# LM704A0_5V0_PINOUT.net
KiCad netlist of a schematic drawn in Altium Designer
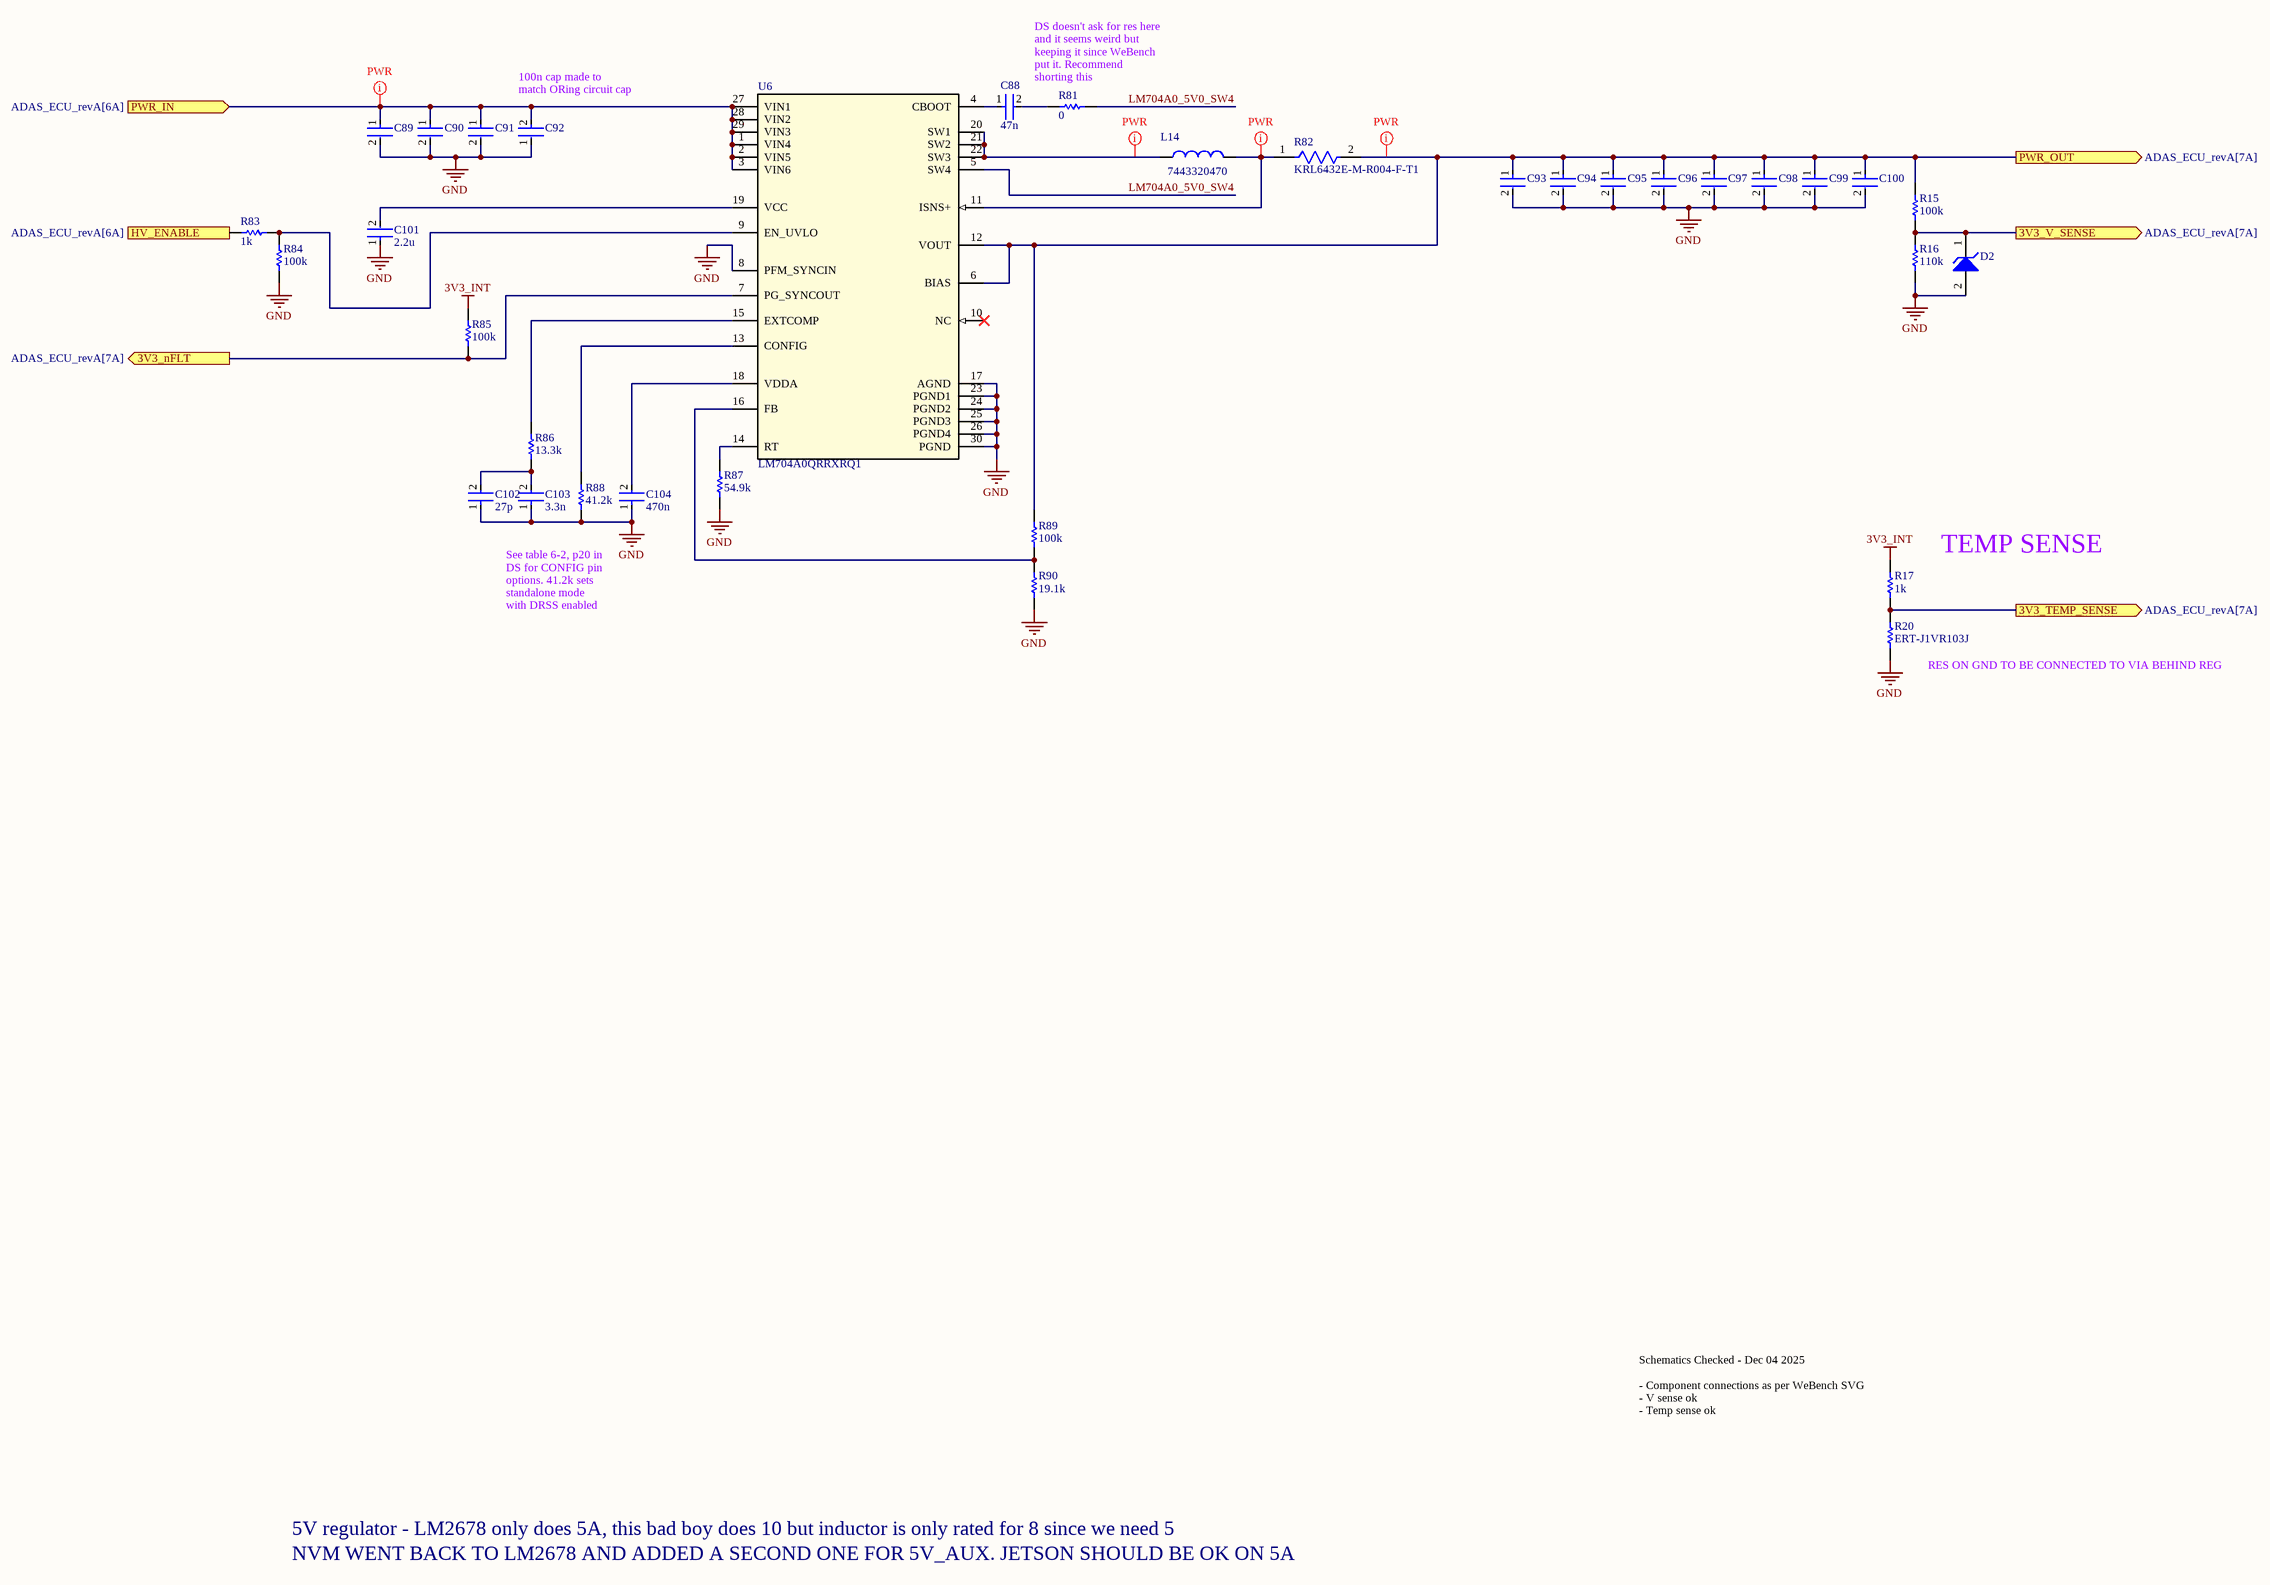
[diagram p0: LM704A0_5V0_PINOUT.SchDoc]

(export (version "E")
  (design (tool "Eeschema 10.0.6"))
  (components
    (comp (ref "C88")
      (value "47n")
      (footprint "FP-0402-L_1_0_0_05-W_0_5-IPC_A")
      (description "LARGE PADS, 0402 CAP, CHANGE COMMENT TO MATCH REAL P/N")
      (libsource (lib "Space Concordia") (part "b4654b650e69147ec39a6b967a45e02"))
    )
    (comp (ref "C89")
      (value "C3225X7R1H106M250AC")
      (footprint "FP-C3225-250-0_4-MFG")
      (description "Multilayer Ceramic Capacitors 10uF ±20% 50V X7R SMD 1210")
      (fields (field (name "TOLERANCE") "20%"))
      (libsource (lib "Altium Content Vault") (part "02cd4be3c70576c341d710602a673aa"))
    )
    (comp (ref "C90")
      (value "C3225X7R1H106M250AC")
      (footprint "FP-C3225-250-0_4-MFG")
      (description "Multilayer Ceramic Capacitors 10uF ±20% 50V X7R SMD 1210")
      (fields (field (name "TOLERANCE") "20%"))
      (libsource (lib "Altium Content Vault") (part "02cd4be3c70576c341d710602a673aa"))
    )
    (comp (ref "C91")
      (value "C3225X7R1H106M250AC")
      (footprint "FP-C3225-250-0_4-MFG")
      (description "Multilayer Ceramic Capacitors 10uF ±20% 50V X7R SMD 1210")
      (fields (field (name "TOLERANCE") "20%"))
      (libsource (lib "Altium Content Vault") (part "02cd4be3c70576c341d710602a673aa"))
    )
    (comp (ref "C92")
      (value "AC1210KKX7R0BB104")
      (footprint "FP-AC1210-0_85-MFG")
      (description "CAP CER 0.1UF 100V X7R 1210")
      (fields (field (name "MANUFACTURER") "Yageo") (field (name "TOLERANCE") "0.1"))
      (libsource (lib "Altium Content Vault") (part "236180d848d6139a670b325ea6854c9"))
    )
    (comp (ref "C93")
      (value "GRM32ER61C476KE15L")
      (footprint "FP-GRM32E-0_3-0_2-IPC_C")
      (description "CAP CER 47UF 16V X5R 1210")
      (fields (field (name "VOLTAGE") "16V") (field (name "TOLERANCE") "10%"))
      (libsource (lib "Altium Content Vault") (part "b4654b650e69147ec39a6b967a45e02"))
    )
    (comp (ref "C94")
      (value "GRM32ER61C476KE15L")
      (footprint "FP-GRM32E-0_3-0_2-IPC_C")
      (description "CAP CER 47UF 16V X5R 1210")
      (fields (field (name "VOLTAGE") "16V") (field (name "TOLERANCE") "10%"))
      (libsource (lib "Altium Content Vault") (part "b4654b650e69147ec39a6b967a45e02"))
    )
    (comp (ref "C95")
      (value "GRM32ER61C476KE15L")
      (footprint "FP-GRM32E-0_3-0_2-IPC_C")
      (description "CAP CER 47UF 16V X5R 1210")
      (fields (field (name "VOLTAGE") "16V") (field (name "TOLERANCE") "10%"))
      (libsource (lib "Altium Content Vault") (part "b4654b650e69147ec39a6b967a45e02"))
    )
    (comp (ref "C96")
      (value "GRM32ER61C476KE15L")
      (footprint "FP-GRM32E-0_3-0_2-IPC_C")
      (description "CAP CER 47UF 16V X5R 1210")
      (fields (field (name "VOLTAGE") "16V") (field (name "TOLERANCE") "10%"))
      (libsource (lib "Altium Content Vault") (part "b4654b650e69147ec39a6b967a45e02"))
    )
    (comp (ref "C97")
      (value "GRM32ER61C476KE15L")
      (footprint "FP-GRM32E-0_3-0_2-IPC_C")
      (description "CAP CER 47UF 16V X5R 1210")
      (fields (field (name "VOLTAGE") "16V") (field (name "TOLERANCE") "10%"))
      (libsource (lib "Altium Content Vault") (part "b4654b650e69147ec39a6b967a45e02"))
    )
    (comp (ref "C98")
      (value "GRM32ER61C476KE15L")
      (footprint "FP-GRM32E-0_3-0_2-IPC_C")
      (description "CAP CER 47UF 16V X5R 1210")
      (fields (field (name "VOLTAGE") "16V") (field (name "TOLERANCE") "10%"))
      (libsource (lib "Altium Content Vault") (part "b4654b650e69147ec39a6b967a45e02"))
    )
    (comp (ref "C99")
      (value "GRM32ER61C476KE15L")
      (footprint "FP-GRM32E-0_3-0_2-IPC_C")
      (description "CAP CER 47UF 16V X5R 1210")
      (fields (field (name "VOLTAGE") "16V") (field (name "TOLERANCE") "10%"))
      (libsource (lib "Altium Content Vault") (part "b4654b650e69147ec39a6b967a45e02"))
    )
    (comp (ref "C100")
      (value "GRM32ER61C476KE15L")
      (footprint "FP-GRM32E-0_3-0_2-IPC_C")
      (description "CAP CER 47UF 16V X5R 1210")
      (fields (field (name "VOLTAGE") "16V") (field (name "TOLERANCE") "10%"))
      (libsource (lib "Altium Content Vault") (part "b4654b650e69147ec39a6b967a45e02"))
    )
    (comp (ref "C101")
      (value "2.2u")
      (footprint "FP-0402-L_1_0_0_05-W_0_5-IPC_A")
      (description "LARGE PADS, 0402 CAP, CHANGE COMMENT TO MATCH REAL P/N")
      (libsource (lib "Space Concordia") (part "b4654b650e69147ec39a6b967a45e02"))
    )
    (comp (ref "C102")
      (value "27p")
      (footprint "FP-0402-L_1_0_0_05-W_0_5-IPC_A")
      (description "LARGE PADS, 0402 CAP, CHANGE COMMENT TO MATCH REAL P/N")
      (libsource (lib "Space Concordia") (part "b4654b650e69147ec39a6b967a45e02"))
    )
    (comp (ref "C103")
      (value "3.3n")
      (footprint "FP-0402-L_1_0_0_05-W_0_5-IPC_A")
      (description "LARGE PADS, 0402 CAP, CHANGE COMMENT TO MATCH REAL P/N")
      (libsource (lib "Space Concordia") (part "b4654b650e69147ec39a6b967a45e02"))
    )
    (comp (ref "C104")
      (value "470n")
      (footprint "FP-0402-L_1_0_0_05-W_0_5-IPC_A")
      (description "LARGE PADS, 0402 CAP, CHANGE COMMENT TO MATCH REAL P/N")
      (libsource (lib "Space Concordia") (part "b4654b650e69147ec39a6b967a45e02"))
    )
    (comp (ref "D2")
      (value "MM5Z3V3T1G")
      (footprint "ONSC-SOD-523-2-502-01_V")
      (description "Zener Voltage Regulator, 500 mW, 2-Pin SOD-523, Pb-Free, Tape and Reel")
      (fields (field (name "MANUFACTURER") "On Semiconductor"))
      (libsource (lib "Altium Content Vault") (part "ONSC-K1A2-2"))
    )
    (comp (ref "L14")
      (value "7443320470")
      (footprint "WE-HCC_1210")
      (description "We-hcc Series, Shielded Wire-wound SMD Inductor With Ferrite Core, 4.7 Uh")
      (libsource (lib "Altium Content Vault") (part "Inductor - 1"))
    )
    (comp (ref "R15")
      (value "100k")
      (footprint "R0603B")
      (description "Resistor")
      (libsource (lib "Space Concordia") (part "Resistor"))
    )
    (comp (ref "R16")
      (value "110k")
      (footprint "R0603B")
      (description "Resistor")
      (libsource (lib "Space Concordia") (part "Resistor"))
    )
    (comp (ref "R17")
      (value "1k")
      (footprint "R0603B")
      (description "Resistor")
      (libsource (lib "Space Concordia") (part "Resistor"))
    )
    (comp (ref "R20")
      (value "ERT-J1VR103J")
      (footprint "RESC1608X90X30ML15T20")
      (fields (field (name "MANUFACTURER") "Panasonic"))
      (libsource (lib "Altium Content Vault") (part "RES"))
    )
    (comp (ref "R81")
      (value "0")
      (footprint "R0603B")
      (description "Resistor")
      (libsource (lib "Space Concordia") (part "Resistor"))
    )
    (comp (ref "R82")
      (value "KRL6432E-M-R004-F-T1")
      (footprint "FP-KRL6432E-MFG")
      (description "KRL6432E-M-R004-F-T1 Metal Foil Low Resistance Chip Resistor (long-side terminal), 2512, RoHS")
      (fields (field (name "TOLERANCE") "1%"))
      (libsource (lib "Altium Content Vault") (part "1029c3af85768c4190bb7ad29bc67b5"))
    )
    (comp (ref "R83")
      (value "1k")
      (footprint "R0603B")
      (description "Resistor")
      (libsource (lib "Space Concordia") (part "Resistor"))
    )
    (comp (ref "R84")
      (value "100k")
      (footprint "R0603B")
      (description "Resistor")
      (libsource (lib "Space Concordia") (part "Resistor"))
    )
    (comp (ref "R85")
      (value "100k")
      (footprint "R0603B")
      (description "Resistor")
      (libsource (lib "Space Concordia") (part "Resistor"))
    )
    (comp (ref "R86")
      (value "13.3k")
      (footprint "R0603B")
      (description "Resistor")
      (libsource (lib "Space Concordia") (part "Resistor"))
    )
    (comp (ref "R87")
      (value "54.9k")
      (footprint "R0603B")
      (description "Resistor")
      (libsource (lib "Space Concordia") (part "Resistor"))
    )
    (comp (ref "R88")
      (value "41.2k")
      (footprint "R0603B")
      (description "Resistor")
      (libsource (lib "Space Concordia") (part "Resistor"))
    )
    (comp (ref "R89")
      (value "100k")
      (footprint "R0603B")
      (description "Resistor")
      (libsource (lib "Space Concordia") (part "Resistor"))
    )
    (comp (ref "R90")
      (value "19.1k")
      (footprint "R0603B")
      (description "Resistor")
      (libsource (lib "Space Concordia") (part "Resistor"))
    )
    (comp (ref "U6")
      (value "LM704A0QRRXRQ1")
      (footprint "LM704A0QRRXRQ1-Footprint-1")
      (libsource (lib "Space Concordia") (part "LM704A0QRRXRQ1"))
    )
  )
  (nets
    (net (code "1") (name "/3V3_TEMP_SENSE") (class "Default")
      (node (ref "R17") (pin "2") (pinfunction "2_2") (pintype "passive"))
      (node (ref "R20") (pin "2") (pinfunction "2_2") (pintype "passive"))
    )
    (net (code "2") (name "/3V3_V_SENSE") (class "Default")
      (node (ref "D2") (pin "1") (pinfunction "K_1") (pintype "passive"))
      (node (ref "R15") (pin "2") (pinfunction "2_2") (pintype "passive"))
      (node (ref "R16") (pin "1") (pinfunction "1_1") (pintype "passive"))
    )
    (net (code "3") (name "/3V3_nFLT") (class "Default")
      (node (ref "R85") (pin "1") (pinfunction "1_1") (pintype "passive"))
      (node (ref "U6") (pin "7") (pinfunction "PG_SYNCOUT_7") (pintype "passive"))
    )
    (net (code "4") (name "/HV_ENABLE") (class "Default")
      (node (ref "R83") (pin "2") (pinfunction "2_2") (pintype "passive"))
    )
    (net (code "5") (name "/LM704A0_5V0_SW4") (class "Default")
      (node (ref "R81") (pin "2") (pinfunction "2_2") (pintype "passive"))
      (node (ref "U6") (pin "5") (pinfunction "SW4_5") (pintype "power_in"))
    )
    (net (code "6") (name "/PWR_IN") (class "Default")
      (node (ref "C89") (pin "1") (pinfunction "1_1") (pintype "passive"))
      (node (ref "C90") (pin "1") (pinfunction "1_1") (pintype "passive"))
      (node (ref "C91") (pin "1") (pinfunction "1_1") (pintype "passive"))
      (node (ref "C92") (pin "2") (pinfunction "2_2") (pintype "passive"))
      (node (ref "U6") (pin "1") (pinfunction "VIN4_1") (pintype "passive"))
      (node (ref "U6") (pin "2") (pinfunction "VIN5_2") (pintype "passive"))
      (node (ref "U6") (pin "27") (pinfunction "VIN1_27") (pintype "power_in"))
      (node (ref "U6") (pin "28") (pinfunction "VIN2_28") (pintype "power_in"))
      (node (ref "U6") (pin "29") (pinfunction "VIN3_29") (pintype "power_in"))
      (node (ref "U6") (pin "3") (pinfunction "VIN6_3") (pintype "power_in"))
    )
    (net (code "7") (name "/PWR_OUT") (class "Default")
      (node (ref "C100") (pin "1") (pinfunction "1_1") (pintype "passive"))
      (node (ref "C93") (pin "1") (pinfunction "1_1") (pintype "passive"))
      (node (ref "C94") (pin "1") (pinfunction "1_1") (pintype "passive"))
      (node (ref "C95") (pin "1") (pinfunction "1_1") (pintype "passive"))
      (node (ref "C96") (pin "1") (pinfunction "1_1") (pintype "passive"))
      (node (ref "C97") (pin "1") (pinfunction "1_1") (pintype "passive"))
      (node (ref "C98") (pin "1") (pinfunction "1_1") (pintype "passive"))
      (node (ref "C99") (pin "1") (pinfunction "1_1") (pintype "passive"))
      (node (ref "R15") (pin "1") (pinfunction "1_1") (pintype "passive"))
      (node (ref "R82") (pin "2") (pinfunction "2_2") (pintype "passive"))
      (node (ref "R89") (pin "1") (pinfunction "1_1") (pintype "passive"))
      (node (ref "U6") (pin "12") (pinfunction "VOUT_12") (pintype "passive"))
      (node (ref "U6") (pin "6") (pinfunction "BIAS_6") (pintype "passive"))
    )
    (net (code "8") (name "3V3_INT") (class "Default")
      (node (ref "R17") (pin "1") (pinfunction "1_1") (pintype "passive"))
      (node (ref "R85") (pin "2") (pinfunction "2_2") (pintype "passive"))
    )
    (net (code "9") (name "GND") (class "Default")
      (node (ref "C100") (pin "2") (pinfunction "2_2") (pintype "passive"))
      (node (ref "C101") (pin "1") (pinfunction "1_1") (pintype "passive"))
      (node (ref "C102") (pin "1") (pinfunction "1_1") (pintype "passive"))
      (node (ref "C103") (pin "1") (pinfunction "1_1") (pintype "passive"))
      (node (ref "C104") (pin "1") (pinfunction "1_1") (pintype "passive"))
      (node (ref "C89") (pin "2") (pinfunction "2_2") (pintype "passive"))
      (node (ref "C90") (pin "2") (pinfunction "2_2") (pintype "passive"))
      (node (ref "C91") (pin "2") (pinfunction "2_2") (pintype "passive"))
      (node (ref "C92") (pin "1") (pinfunction "1_1") (pintype "passive"))
      (node (ref "C93") (pin "2") (pinfunction "2_2") (pintype "passive"))
      (node (ref "C94") (pin "2") (pinfunction "2_2") (pintype "passive"))
      (node (ref "C95") (pin "2") (pinfunction "2_2") (pintype "passive"))
      (node (ref "C96") (pin "2") (pinfunction "2_2") (pintype "passive"))
      (node (ref "C97") (pin "2") (pinfunction "2_2") (pintype "passive"))
      (node (ref "C98") (pin "2") (pinfunction "2_2") (pintype "passive"))
      (node (ref "C99") (pin "2") (pinfunction "2_2") (pintype "passive"))
      (node (ref "D2") (pin "2") (pinfunction "A_2") (pintype "passive"))
      (node (ref "R16") (pin "2") (pinfunction "2_2") (pintype "passive"))
      (node (ref "R20") (pin "1") (pinfunction "1_1") (pintype "passive"))
      (node (ref "R84") (pin "1") (pinfunction "1_1") (pintype "passive"))
      (node (ref "R87") (pin "2") (pinfunction "2_2") (pintype "passive"))
      (node (ref "R88") (pin "2") (pinfunction "2_2") (pintype "passive"))
      (node (ref "R90") (pin "2") (pinfunction "2_2") (pintype "passive"))
      (node (ref "U6") (pin "17") (pinfunction "AGND_17") (pintype "passive"))
      (node (ref "U6") (pin "23") (pinfunction "PGND1_23") (pintype "passive"))
      (node (ref "U6") (pin "24") (pinfunction "PGND2_24") (pintype "passive"))
      (node (ref "U6") (pin "25") (pinfunction "PGND3_25") (pintype "power_in"))
      (node (ref "U6") (pin "26") (pinfunction "PGND4_26") (pintype "power_in"))
      (node (ref "U6") (pin "30") (pinfunction "PGND_30") (pintype "power_in"))
      (node (ref "U6") (pin "8") (pinfunction "PFM_SYNCIN_8") (pintype "power_in"))
    )
    (net (code "10") (name "Net-(C88-Pad2)") (class "Default")
      (node (ref "C88") (pin "2") (pinfunction "2_2") (pintype "passive"))
      (node (ref "R81") (pin "1") (pinfunction "1_1") (pintype "passive"))
    )
    (net (code "11") (name "Net-(C102-Pad2)") (class "Default")
      (node (ref "C102") (pin "2") (pinfunction "2_2") (pintype "passive"))
      (node (ref "C103") (pin "2") (pinfunction "2_2") (pintype "passive"))
      (node (ref "R86") (pin "1") (pinfunction "1_1") (pintype "passive"))
    )
    (net (code "12") (name "Net-(U6-CBOOT)") (class "Default")
      (node (ref "C88") (pin "1") (pinfunction "1_1") (pintype "passive"))
      (node (ref "U6") (pin "4") (pinfunction "CBOOT_4") (pintype "power_in"))
    )
    (net (code "13") (name "Net-(U6-CONFIG)") (class "Default")
      (node (ref "R88") (pin "1") (pinfunction "1_1") (pintype "passive"))
      (node (ref "U6") (pin "13") (pinfunction "CONFIG_13") (pintype "passive"))
    )
    (net (code "14") (name "Net-(U6-EN_UVLO)") (class "Default")
      (node (ref "R83") (pin "1") (pinfunction "1_1") (pintype "passive"))
      (node (ref "R84") (pin "2") (pinfunction "2_2") (pintype "passive"))
      (node (ref "U6") (pin "9") (pinfunction "EN_UVLO_9") (pintype "open_collector"))
    )
    (net (code "15") (name "Net-(U6-EXTCOMP)") (class "Default")
      (node (ref "R86") (pin "2") (pinfunction "2_2") (pintype "passive"))
      (node (ref "U6") (pin "15") (pinfunction "EXTCOMP_15") (pintype "passive"))
    )
    (net (code "16") (name "Net-(U6-FB)") (class "Default")
      (node (ref "R89") (pin "2") (pinfunction "2_2") (pintype "passive"))
      (node (ref "R90") (pin "1") (pinfunction "1_1") (pintype "passive"))
      (node (ref "U6") (pin "16") (pinfunction "FB_16") (pintype "passive"))
    )
    (net (code "17") (name "Net-(U6-ISNS+)") (class "Default")
      (node (ref "L14") (pin "2") (pinfunction "2_2") (pintype "passive"))
      (node (ref "R82") (pin "1") (pinfunction "1_1") (pintype "passive"))
      (node (ref "U6") (pin "11") (pinfunction "ISNS+_11") (pintype "input"))
    )
    (net (code "18") (name "Net-(U6-RT)") (class "Default")
      (node (ref "R87") (pin "1") (pinfunction "1_1") (pintype "passive"))
      (node (ref "U6") (pin "14") (pinfunction "RT_14") (pintype "passive"))
    )
    (net (code "19") (name "Net-(U6-SW1)") (class "Default")
      (node (ref "L14") (pin "1") (pinfunction "1_1") (pintype "passive"))
      (node (ref "U6") (pin "20") (pinfunction "SW1_20") (pintype "power_in"))
      (node (ref "U6") (pin "21") (pinfunction "SW2_21") (pintype "power_in"))
      (node (ref "U6") (pin "22") (pinfunction "SW3_22") (pintype "passive"))
    )
    (net (code "20") (name "Net-(U6-VCC)") (class "Default")
      (node (ref "C101") (pin "2") (pinfunction "2_2") (pintype "passive"))
      (node (ref "U6") (pin "19") (pinfunction "VCC_19") (pintype "power_in"))
    )
    (net (code "21") (name "Net-(U6-VDDA)") (class "Default")
      (node (ref "C104") (pin "2") (pinfunction "2_2") (pintype "passive"))
      (node (ref "U6") (pin "18") (pinfunction "VDDA_18") (pintype "passive"))
    )
    (net (code "22") (name "unconnected-(U6-NC-Pad10)") (class "Default")
      (node (ref "U6") (pin "10") (pinfunction "NC_10") (pintype "input+no_connect"))
    )
  )
)
